# AnalogSensor.net
KiCad netlist of a schematic drawn in Altium Designer
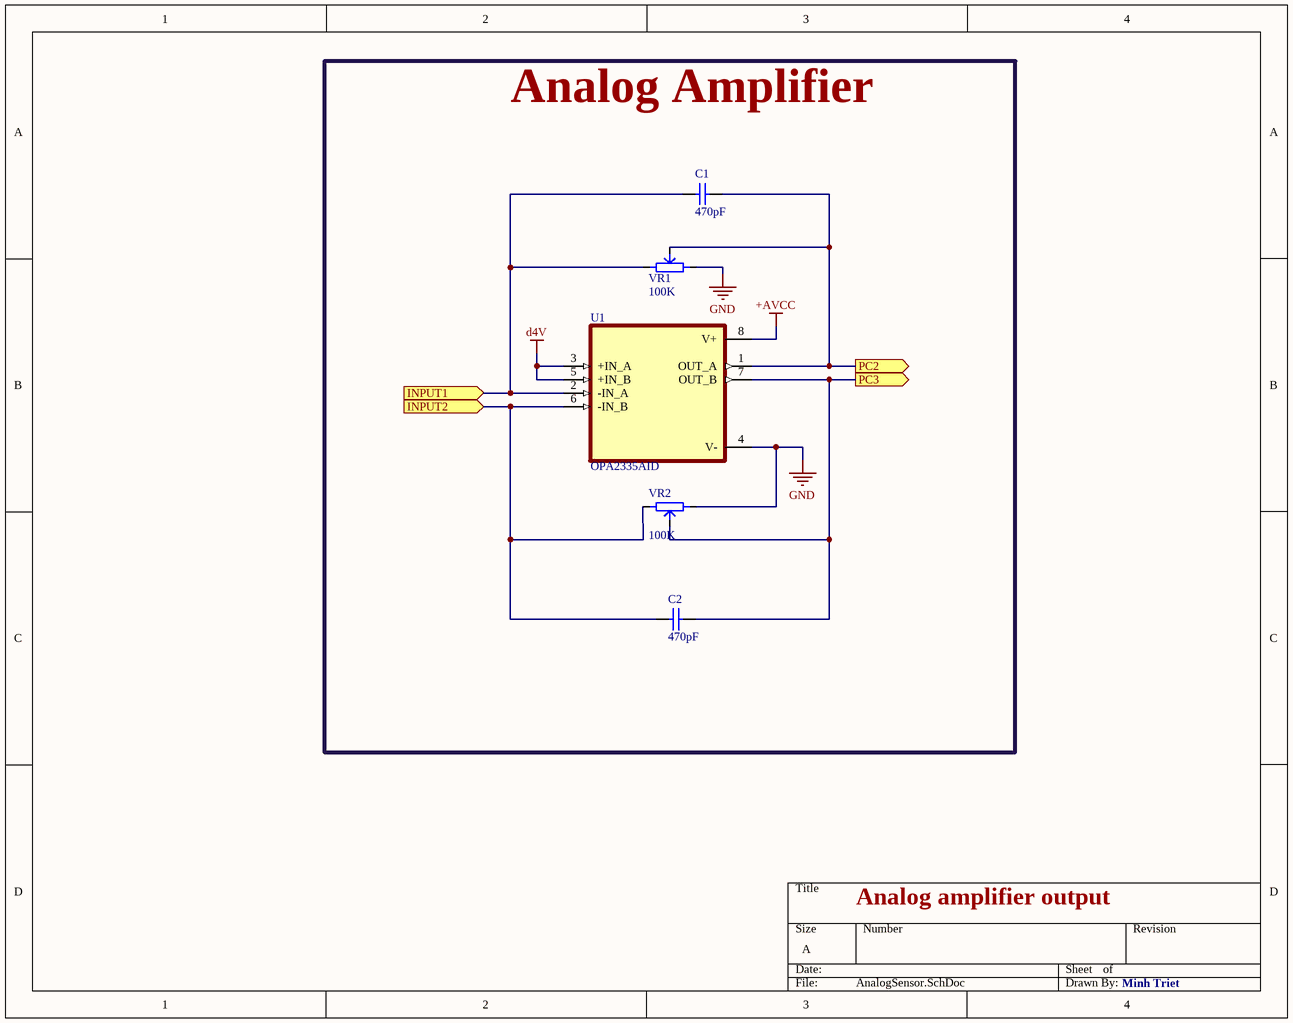
[diagram p0: AnalogSensor.SchDoc]

(export (version "E")
  (design (tool "Eeschema 10.0.6"))
  (components
    (comp (ref "C1")
      (value "470pF")
      (footprint "tu 0603")
      (description "Dán")
      (libsource (lib "Altium_Lib_by_KhueNguyenCreator") (part "Tu 0603 470pF 50V 10%"))
    )
    (comp (ref "C2")
      (value "470pF")
      (footprint "tu 0603")
      (description "Dán")
      (libsource (lib "Altium_Lib_by_KhueNguyenCreator") (part "Tu 0603 470pF 50V 10%"))
    )
    (comp (ref "U1")
      (value "OPA2335AID")
      (footprint "SOIC127P599X175-8N")
      (fields (field (name "MF") "{'manufacturer': u'Texas Instruments'}"))
      (libsource (lib "SnapEDA_Library") (part "OPA2335AID"))
    )
    (comp (ref "VR1")
      (value "100K")
      (footprint "Bien Tro Tam Giac Dung")
      (description "Cắm")
      (libsource (lib "Altium_Lib_by_KhueNguyenCreator") (part "Bien tro tam giac 100K Dung"))
    )
    (comp (ref "VR2")
      (value "100K")
      (footprint "Bien Tro Tam Giac Dung")
      (description "Cắm")
      (libsource (lib "Altium_Lib_by_KhueNguyenCreator") (part "Bien tro tam giac 100K Dung"))
    )
  )
  (nets
    (net (code "1") (name "+AVCC") (class "Default")
      (node (ref "U1") (pin "8") (pinfunction "V+_8") (pintype "power_in"))
    )
    (net (code "2") (name "/INPUT1") (class "Default")
      (node (ref "C1") (pin "2") (pinfunction "2_2") (pintype "passive"))
      (node (ref "U1") (pin "2") (pinfunction "-IN_A_2") (pintype "input"))
      (node (ref "VR1") (pin "1") (pinfunction "1_1") (pintype "passive"))
    )
    (net (code "3") (name "/INPUT2") (class "Default")
      (node (ref "C2") (pin "2") (pinfunction "2_2") (pintype "passive"))
      (node (ref "U1") (pin "6") (pinfunction "-IN_B_6") (pintype "input"))
      (node (ref "VR2") (pin "3") (pinfunction "3_3") (pintype "passive"))
    )
    (net (code "4") (name "/PC2") (class "Default")
      (node (ref "C1") (pin "1") (pinfunction "1_1") (pintype "passive"))
      (node (ref "U1") (pin "1") (pinfunction "OUT_A_1") (pintype "output"))
      (node (ref "VR1") (pin "2") (pinfunction "2_2") (pintype "passive"))
    )
    (net (code "5") (name "/PC3") (class "Default")
      (node (ref "C2") (pin "1") (pinfunction "1_1") (pintype "passive"))
      (node (ref "U1") (pin "7") (pinfunction "OUT_B_7") (pintype "output"))
      (node (ref "VR2") (pin "2") (pinfunction "2_2") (pintype "passive"))
    )
    (net (code "6") (name "GND") (class "Default")
      (node (ref "U1") (pin "4") (pinfunction "V-_4") (pintype "power_in"))
      (node (ref "VR1") (pin "3") (pinfunction "3_3") (pintype "passive"))
      (node (ref "VR2") (pin "1") (pinfunction "1_1") (pintype "passive"))
    )
    (net (code "7") (name "d4V") (class "Default")
      (node (ref "U1") (pin "3") (pinfunction "+IN_A_3") (pintype "input"))
      (node (ref "U1") (pin "5") (pinfunction "+IN_B_5") (pintype "input"))
    )
  )
)
